# Power_Supply_Board.net
KiCad netlist of a schematic drawn in EAGLE
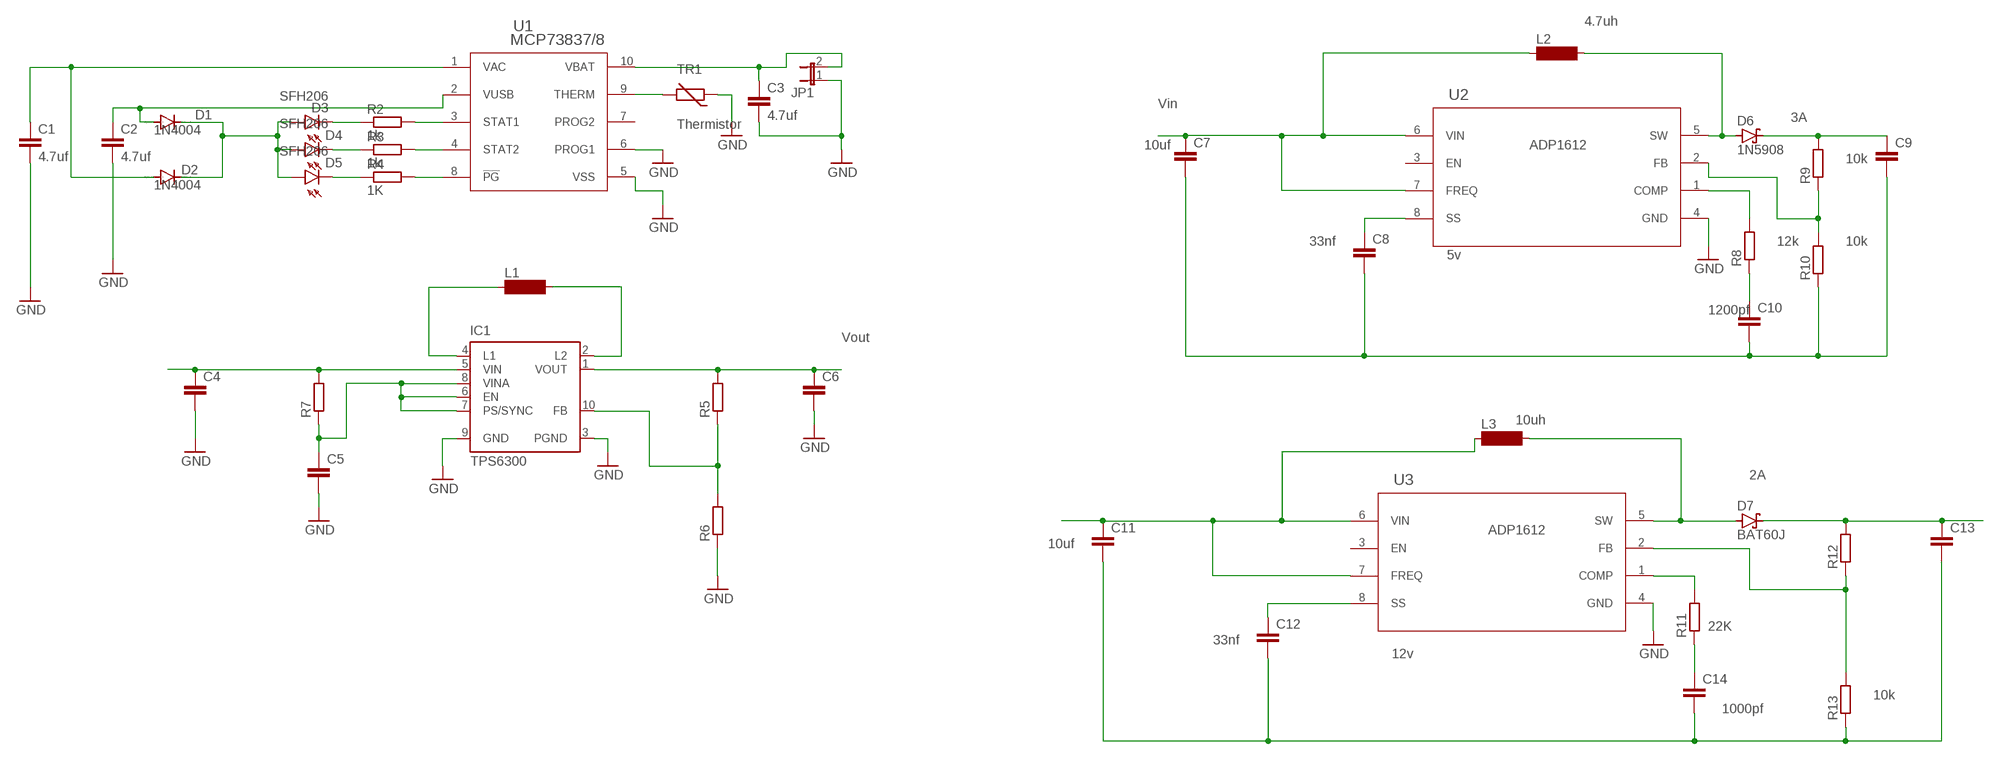
[diagram p0: schematic, sheet 1]

(export (version "E")
  (design (tool "Eeschema 10.0.6"))
  (components
    (comp (ref "C1")
      (value "4.7uf")
      (footprint "eagle-import:C2.5-3")
      (libsource (lib "eagle-import") (part "C2,5-3"))
    )
    (comp (ref "C2")
      (value "4.7uf")
      (footprint "eagle-import:C2.5-3")
      (libsource (lib "eagle-import") (part "C2,5-3"))
    )
    (comp (ref "C3")
      (value "4.7uf")
      (footprint "eagle-import:C2.5-3")
      (libsource (lib "eagle-import") (part "C2,5-3"))
    )
    (comp (ref "C4")
      (value "C2,5-3")
      (footprint "eagle-import:C2.5-3")
      (libsource (lib "eagle-import") (part "C2,5-3"))
    )
    (comp (ref "C5")
      (value "C2,5-3")
      (footprint "eagle-import:C2.5-3")
      (libsource (lib "eagle-import") (part "C2,5-3"))
    )
    (comp (ref "C6")
      (value "C2,5-3")
      (footprint "eagle-import:C2.5-3")
      (libsource (lib "eagle-import") (part "C2,5-3"))
    )
    (comp (ref "C7")
      (value "C2.5/2")
      (footprint "eagle-import:C2.5-2")
      (libsource (lib "eagle-import") (part "C2.5/2"))
    )
    (comp (ref "C8")
      (value "C2.5/2")
      (footprint "eagle-import:C2.5-2")
      (libsource (lib "eagle-import") (part "C2.5/2"))
    )
    (comp (ref "C9")
      (value "C2.5/2")
      (footprint "eagle-import:C2.5-2")
      (libsource (lib "eagle-import") (part "C2.5/2"))
    )
    (comp (ref "C10")
      (value "C2.5/2")
      (footprint "eagle-import:C2.5-2")
      (libsource (lib "eagle-import") (part "C2.5/2"))
    )
    (comp (ref "C11")
      (value "C2.5/2")
      (footprint "eagle-import:C2.5-2")
      (libsource (lib "eagle-import") (part "C2.5/2"))
    )
    (comp (ref "C12")
      (value "C2.5/2")
      (footprint "eagle-import:C2.5-2")
      (libsource (lib "eagle-import") (part "C2.5/2"))
    )
    (comp (ref "C13")
      (value "C2.5/2")
      (footprint "eagle-import:C2.5-2")
      (libsource (lib "eagle-import") (part "C2.5/2"))
    )
    (comp (ref "C14")
      (value "C2.5/2")
      (footprint "eagle-import:C2.5-2")
      (libsource (lib "eagle-import") (part "C2.5/2"))
    )
    (comp (ref "D1")
      (value "1N4004")
      (footprint "eagle-import:DO41-10")
      (libsource (lib "eagle-import") (part "1N4004"))
    )
    (comp (ref "D2")
      (value "1N4004")
      (footprint "eagle-import:DO41-10")
      (libsource (lib "eagle-import") (part "1N4004"))
    )
    (comp (ref "D3")
      (value "SFH206")
      (footprint "eagle-import:SFH206")
      (fields (field (name "MPN") "SFH206K"))
      (libsource (lib "eagle-import") (part "SFH206"))
    )
    (comp (ref "D4")
      (value "SFH206")
      (footprint "eagle-import:SFH206")
      (fields (field (name "MPN") "SFH206K"))
      (libsource (lib "eagle-import") (part "SFH206"))
    )
    (comp (ref "D5")
      (value "SFH206")
      (footprint "eagle-import:SFH206")
      (fields (field (name "MPN") "SFH206K"))
      (libsource (lib "eagle-import") (part "SFH206"))
    )
    (comp (ref "D6")
      (value "1N5908")
      (footprint "eagle-import:C4111-15")
      (libsource (lib "eagle-import") (part "1N5908"))
    )
    (comp (ref "D7")
      (value "BAT60J")
      (footprint "eagle-import:SOD323_ST")
      (libsource (lib "eagle-import") (part "BAT60J"))
    )
    (comp (ref "IC1")
      (value "TPS6300")
      (footprint "eagle-import:DRC-S-PVSON-N10")
      (fields (field (name "MPN") "TPS63000DRCTG4"))
      (libsource (lib "eagle-import") (part "TPS6300"))
    )
    (comp (ref "JP1")
      (value "JP1E")
      (footprint "eagle-import:JP1")
      (libsource (lib "eagle-import") (part "JP1E"))
    )
    (comp (ref "L1")
      (value "SM-NE29")
      (footprint "eagle-import:SM-NE29")
      (libsource (lib "eagle-import") (part "SM-NE29"))
    )
    (comp (ref "L2")
      (value "SM-NE29")
      (footprint "eagle-import:SM-NE29")
      (libsource (lib "eagle-import") (part "SM-NE29"))
    )
    (comp (ref "L3")
      (value "SM-NE29")
      (footprint "eagle-import:SM-NE29")
      (libsource (lib "eagle-import") (part "SM-NE29"))
    )
    (comp (ref "R2")
      (value "1k")
      (footprint "eagle-import:0204_5")
      (libsource (lib "eagle-import") (part "R-EU_0204/5"))
    )
    (comp (ref "R3")
      (value "1k")
      (footprint "eagle-import:0204_5")
      (libsource (lib "eagle-import") (part "R-EU_0204/5"))
    )
    (comp (ref "R4")
      (value "1K")
      (footprint "eagle-import:0204_5")
      (libsource (lib "eagle-import") (part "R-EU_0204/5"))
    )
    (comp (ref "R5")
      (value "R-EU_0204/2V")
      (footprint "eagle-import:0204V")
      (libsource (lib "eagle-import") (part "R-EU_0204/2V"))
    )
    (comp (ref "R6")
      (value "R-EU_0204/2V")
      (footprint "eagle-import:0204V")
      (libsource (lib "eagle-import") (part "R-EU_0204/2V"))
    )
    (comp (ref "R7")
      (value "R-EU_0204/2V")
      (footprint "eagle-import:0204V")
      (libsource (lib "eagle-import") (part "R-EU_0204/2V"))
    )
    (comp (ref "R8")
      (value "R-EU_V235/17")
      (footprint "eagle-import:V235_17")
      (libsource (lib "eagle-import") (part "R-EU_V235/17"))
    )
    (comp (ref "R9")
      (value "R-EU_V235/17")
      (footprint "eagle-import:V235_17")
      (libsource (lib "eagle-import") (part "R-EU_V235/17"))
    )
    (comp (ref "R10")
      (value "R-EU_V235/17")
      (footprint "eagle-import:V235_17")
      (libsource (lib "eagle-import") (part "R-EU_V235/17"))
    )
    (comp (ref "R11")
      (value "R-EU_0207/15")
      (footprint "eagle-import:0207_15")
      (libsource (lib "eagle-import") (part "R-EU_0207/15"))
    )
    (comp (ref "R12")
      (value "R-EU_0207/15")
      (footprint "eagle-import:0207_15")
      (libsource (lib "eagle-import") (part "R-EU_0207/15"))
    )
    (comp (ref "R13")
      (value "R-EU_0207/15")
      (footprint "eagle-import:0207_15")
      (libsource (lib "eagle-import") (part "R-EU_0207/15"))
    )
    (comp (ref "TR1")
      (value "Thermistor")
      (footprint "eagle-import:R-5")
      (libsource (lib "eagle-import") (part "THERMISTOR_R-5"))
    )
    (comp (ref "U1")
      (value "MCP73837/8")
      (footprint "eagle-import:MSOP10_MC_MCH")
      (fields (field (name "MANUFACTURER_PART_NUMBER") "MCP73837-FCI/UN"))
      (libsource (lib "eagle-import") (part "MCP73837-FCI/UN"))
    )
    (comp (ref "U2")
      (value "ADP1612")
      (footprint "eagle-import:RM_8_ADI")
      (fields (field (name "MANUFACTURER_PART_NUMBER") "ADP1612ARMZ-R7"))
      (libsource (lib "eagle-import") (part "ADP1612"))
    )
    (comp (ref "U3")
      (value "ADP1612RM_8_ADI-L")
      (footprint "eagle-import:RM_8_ADI-L")
      (fields (field (name "MANUFACTURER_PART_NUMBER") "ADP1612ARMZ-R7"))
      (libsource (lib "eagle-import") (part "ADP1612RM_8_ADI-L"))
    )
  )
  (nets
    (net (code "1") (name "GND") (class "Default")
      (node (ref "C1") (pin "2") (pinfunction "2_2") (pintype "passive"))
      (node (ref "C2") (pin "2") (pinfunction "2_2") (pintype "passive"))
      (node (ref "C3") (pin "2") (pinfunction "2_2") (pintype "passive"))
      (node (ref "C4") (pin "2") (pinfunction "2_2") (pintype "passive"))
      (node (ref "C5") (pin "2") (pinfunction "2_2") (pintype "passive"))
      (node (ref "C6") (pin "2") (pinfunction "2_2") (pintype "passive"))
      (node (ref "IC1") (pin "3") (pinfunction "PGND_3") (pintype "power_in"))
      (node (ref "IC1") (pin "9") (pinfunction "GND_9") (pintype "power_in"))
      (node (ref "JP1") (pin "1") (pinfunction "1_1") (pintype "passive"))
      (node (ref "R6") (pin "1") (pinfunction "1_1") (pintype "passive"))
      (node (ref "TR1") (pin "1") (pinfunction "1_1") (pintype "passive"))
      (node (ref "U1") (pin "5") (pinfunction "VSS_5") (pintype "passive"))
      (node (ref "U1") (pin "6") (pinfunction "PROG1_6") (pintype "passive"))
      (node (ref "U2") (pin "4") (pinfunction "GND_4") (pintype "passive"))
      (node (ref "U3") (pin "4") (pinfunction "GND_4") (pintype "passive"))
    )
    (net (code "2") (name "Net-(C9-Pad1)") (class "Default")
      (node (ref "C9") (pin "1") (pinfunction "1_1") (pintype "passive"))
      (node (ref "D6") (pin "C") (pinfunction "C_C") (pintype "passive"))
      (node (ref "R9") (pin "2") (pinfunction "2_2") (pintype "passive"))
    )
    (net (code "3") (name "Net-(C10-Pad1)") (class "Default")
      (node (ref "C10") (pin "1") (pinfunction "1_1") (pintype "passive"))
      (node (ref "R8") (pin "1") (pinfunction "1_1") (pintype "passive"))
    )
    (net (code "4") (name "Net-(C10-Pad2)") (class "Default")
      (node (ref "C10") (pin "2") (pinfunction "2_2") (pintype "passive"))
      (node (ref "C7") (pin "2") (pinfunction "2_2") (pintype "passive"))
      (node (ref "C8") (pin "2") (pinfunction "2_2") (pintype "passive"))
      (node (ref "C9") (pin "2") (pinfunction "2_2") (pintype "passive"))
      (node (ref "R10") (pin "1") (pinfunction "1_1") (pintype "passive"))
    )
    (net (code "5") (name "Net-(C11-Pad2)") (class "Default")
      (node (ref "C11") (pin "2") (pinfunction "2_2") (pintype "passive"))
      (node (ref "C12") (pin "2") (pinfunction "2_2") (pintype "passive"))
      (node (ref "C13") (pin "2") (pinfunction "2_2") (pintype "passive"))
      (node (ref "C14") (pin "2") (pinfunction "2_2") (pintype "passive"))
      (node (ref "R13") (pin "1") (pinfunction "1_1") (pintype "passive"))
    )
    (net (code "6") (name "Net-(C13-Pad1)") (class "Default")
      (node (ref "C13") (pin "1") (pinfunction "1_1") (pintype "passive"))
      (node (ref "D7") (pin "C") (pinfunction "C_C") (pintype "passive"))
      (node (ref "R12") (pin "2") (pinfunction "2_2") (pintype "passive"))
    )
    (net (code "7") (name "Net-(C14-Pad1)") (class "Default")
      (node (ref "C14") (pin "1") (pinfunction "1_1") (pintype "passive"))
      (node (ref "R11") (pin "1") (pinfunction "1_1") (pintype "passive"))
    )
    (net (code "8") (name "Net-(D1-PadC)") (class "Default")
      (node (ref "D1") (pin "C") (pinfunction "C_C") (pintype "passive"))
      (node (ref "D2") (pin "C") (pinfunction "C_C") (pintype "passive"))
      (node (ref "D3") (pin "A") (pinfunction "A_A") (pintype "passive"))
      (node (ref "D4") (pin "A") (pinfunction "A_A") (pintype "passive"))
      (node (ref "D5") (pin "A") (pinfunction "A_A") (pintype "passive"))
    )
    (net (code "9") (name "Net-(D3-C)") (class "Default")
      (node (ref "D3") (pin "K") (pinfunction "C_K") (pintype "passive"))
      (node (ref "R2") (pin "1") (pinfunction "1_1") (pintype "passive"))
    )
    (net (code "10") (name "Net-(D4-C)") (class "Default")
      (node (ref "D4") (pin "K") (pinfunction "C_K") (pintype "passive"))
      (node (ref "R3") (pin "1") (pinfunction "1_1") (pintype "passive"))
    )
    (net (code "11") (name "Net-(D5-C)") (class "Default")
      (node (ref "D5") (pin "K") (pinfunction "C_K") (pintype "passive"))
      (node (ref "R4") (pin "1") (pinfunction "1_1") (pintype "passive"))
    )
    (net (code "12") (name "Net-(IC1A-EN)") (class "Default")
      (node (ref "C5") (pin "1") (pinfunction "1_1") (pintype "passive"))
      (node (ref "IC1") (pin "6") (pinfunction "EN_6") (pintype "input"))
      (node (ref "IC1") (pin "7") (pinfunction "PS/SYNC_7") (pintype "input"))
      (node (ref "IC1") (pin "8") (pinfunction "VINA_8") (pintype "input"))
      (node (ref "R7") (pin "1") (pinfunction "1_1") (pintype "passive"))
    )
    (net (code "13") (name "Net-(IC1A-FB)") (class "Default")
      (node (ref "IC1") (pin "10") (pinfunction "FB_10") (pintype "input"))
      (node (ref "R5") (pin "1") (pinfunction "1_1") (pintype "passive"))
      (node (ref "R6") (pin "2") (pinfunction "2_2") (pintype "passive"))
    )
    (net (code "14") (name "Net-(IC1A-L1)") (class "Default")
      (node (ref "IC1") (pin "4") (pinfunction "L1_4") (pintype "passive"))
      (node (ref "L1") (pin "1") (pinfunction "1_1") (pintype "passive"))
    )
    (net (code "15") (name "Net-(IC1A-L2)") (class "Default")
      (node (ref "IC1") (pin "2") (pinfunction "L2_2") (pintype "passive"))
      (node (ref "L1") (pin "2") (pinfunction "2_2") (pintype "passive"))
    )
    (net (code "16") (name "Net-(IC1A-VIN)") (class "Default")
      (node (ref "C4") (pin "1") (pinfunction "1_1") (pintype "passive"))
      (node (ref "IC1") (pin "5") (pinfunction "VIN_5") (pintype "input"))
      (node (ref "R7") (pin "2") (pinfunction "2_2") (pintype "passive"))
    )
    (net (code "17") (name "Net-(IC1A-VOUT)") (class "Default")
      (node (ref "C6") (pin "1") (pinfunction "1_1") (pintype "passive"))
      (node (ref "IC1") (pin "1") (pinfunction "VOUT_1") (pintype "output"))
      (node (ref "R5") (pin "2") (pinfunction "2_2") (pintype "passive"))
    )
    (net (code "18") (name "Net-(U1-STAT1)") (class "Default")
      (node (ref "R2") (pin "2") (pinfunction "2_2") (pintype "passive"))
      (node (ref "U1") (pin "3") (pinfunction "STAT1_3") (pintype "passive"))
    )
    (net (code "19") (name "Net-(U1-STAT2)") (class "Default")
      (node (ref "R3") (pin "2") (pinfunction "2_2") (pintype "passive"))
      (node (ref "U1") (pin "4") (pinfunction "STAT2_4") (pintype "passive"))
    )
    (net (code "20") (name "Net-(U1-THERM)") (class "Default")
      (node (ref "TR1") (pin "2") (pinfunction "2_2") (pintype "passive"))
      (node (ref "U1") (pin "9") (pinfunction "THERM_9") (pintype "passive"))
    )
    (net (code "21") (name "Net-(U1-VAC)") (class "Default")
      (node (ref "C1") (pin "1") (pinfunction "1_1") (pintype "passive"))
      (node (ref "D2") (pin "A") (pinfunction "A_A") (pintype "passive"))
      (node (ref "U1") (pin "1") (pinfunction "VAC_1") (pintype "passive"))
    )
    (net (code "22") (name "Net-(U1-VBAT)") (class "Default")
      (node (ref "C3") (pin "1") (pinfunction "1_1") (pintype "passive"))
      (node (ref "JP1") (pin "2") (pinfunction "2_2") (pintype "passive"))
      (node (ref "U1") (pin "10") (pinfunction "VBAT_10") (pintype "passive"))
    )
    (net (code "23") (name "Net-(U1-VUSB)") (class "Default")
      (node (ref "C2") (pin "1") (pinfunction "1_1") (pintype "passive"))
      (node (ref "D1") (pin "A") (pinfunction "A_A") (pintype "passive"))
      (node (ref "U1") (pin "2") (pinfunction "VUSB_2") (pintype "passive"))
    )
    (net (code "24") (name "Net-(U1-~{PG})") (class "Default")
      (node (ref "R4") (pin "2") (pinfunction "2_2") (pintype "passive"))
      (node (ref "U1") (pin "8") (pinfunction "~{PG}_8") (pintype "passive"))
    )
    (net (code "25") (name "Net-(U2-COMP)") (class "Default")
      (node (ref "R8") (pin "2") (pinfunction "2_2") (pintype "passive"))
      (node (ref "U2") (pin "1") (pinfunction "COMP_1") (pintype "passive"))
    )
    (net (code "26") (name "Net-(U2-FB)") (class "Default")
      (node (ref "R10") (pin "2") (pinfunction "2_2") (pintype "passive"))
      (node (ref "R9") (pin "1") (pinfunction "1_1") (pintype "passive"))
      (node (ref "U2") (pin "2") (pinfunction "FB_2") (pintype "passive"))
    )
    (net (code "27") (name "Net-(U2-FREQ)") (class "Default")
      (node (ref "C7") (pin "1") (pinfunction "1_1") (pintype "passive"))
      (node (ref "L2") (pin "1") (pinfunction "1_1") (pintype "passive"))
      (node (ref "U2") (pin "6") (pinfunction "VIN_6") (pintype "passive"))
      (node (ref "U2") (pin "7") (pinfunction "FREQ_7") (pintype "passive"))
    )
    (net (code "28") (name "Net-(U2-SS)") (class "Default")
      (node (ref "C8") (pin "1") (pinfunction "1_1") (pintype "passive"))
      (node (ref "U2") (pin "8") (pinfunction "SS_8") (pintype "passive"))
    )
    (net (code "29") (name "Net-(U2-SW)") (class "Default")
      (node (ref "D6") (pin "A") (pinfunction "A_A") (pintype "passive"))
      (node (ref "L2") (pin "2") (pinfunction "2_2") (pintype "passive"))
      (node (ref "U2") (pin "5") (pinfunction "SW_5") (pintype "passive"))
    )
    (net (code "30") (name "Net-(U3-COMP)") (class "Default")
      (node (ref "R11") (pin "2") (pinfunction "2_2") (pintype "passive"))
      (node (ref "U3") (pin "1") (pinfunction "COMP_1") (pintype "passive"))
    )
    (net (code "31") (name "Net-(U3-FB)") (class "Default")
      (node (ref "R12") (pin "1") (pinfunction "1_1") (pintype "passive"))
      (node (ref "R13") (pin "2") (pinfunction "2_2") (pintype "passive"))
      (node (ref "U3") (pin "2") (pinfunction "FB_2") (pintype "passive"))
    )
    (net (code "32") (name "Net-(U3-FREQ)") (class "Default")
      (node (ref "C11") (pin "1") (pinfunction "1_1") (pintype "passive"))
      (node (ref "L3") (pin "1") (pinfunction "1_1") (pintype "passive"))
      (node (ref "U3") (pin "6") (pinfunction "VIN_6") (pintype "passive"))
      (node (ref "U3") (pin "7") (pinfunction "FREQ_7") (pintype "passive"))
    )
    (net (code "33") (name "Net-(U3-SS)") (class "Default")
      (node (ref "C12") (pin "1") (pinfunction "1_1") (pintype "passive"))
      (node (ref "U3") (pin "8") (pinfunction "SS_8") (pintype "passive"))
    )
    (net (code "34") (name "Net-(U3-SW)") (class "Default")
      (node (ref "D7") (pin "A") (pinfunction "A_A") (pintype "passive"))
      (node (ref "L3") (pin "2") (pinfunction "2_2") (pintype "passive"))
      (node (ref "U3") (pin "5") (pinfunction "SW_5") (pintype "passive"))
    )
    (net (code "35") (name "unconnected-(U1-PROG2-Pad7)") (class "Default")
      (node (ref "U1") (pin "7") (pinfunction "PROG2_7") (pintype "passive"))
    )
    (net (code "36") (name "unconnected-(U2-EN-Pad3)") (class "Default")
      (node (ref "U2") (pin "3") (pinfunction "EN_3") (pintype "passive"))
    )
    (net (code "37") (name "unconnected-(U3-EN-Pad3)") (class "Default")
      (node (ref "U3") (pin "3") (pinfunction "EN_3") (pintype "passive"))
    )
  )
)
